# M701X.net
KiCad netlist of a schematic drawn in EAGLE
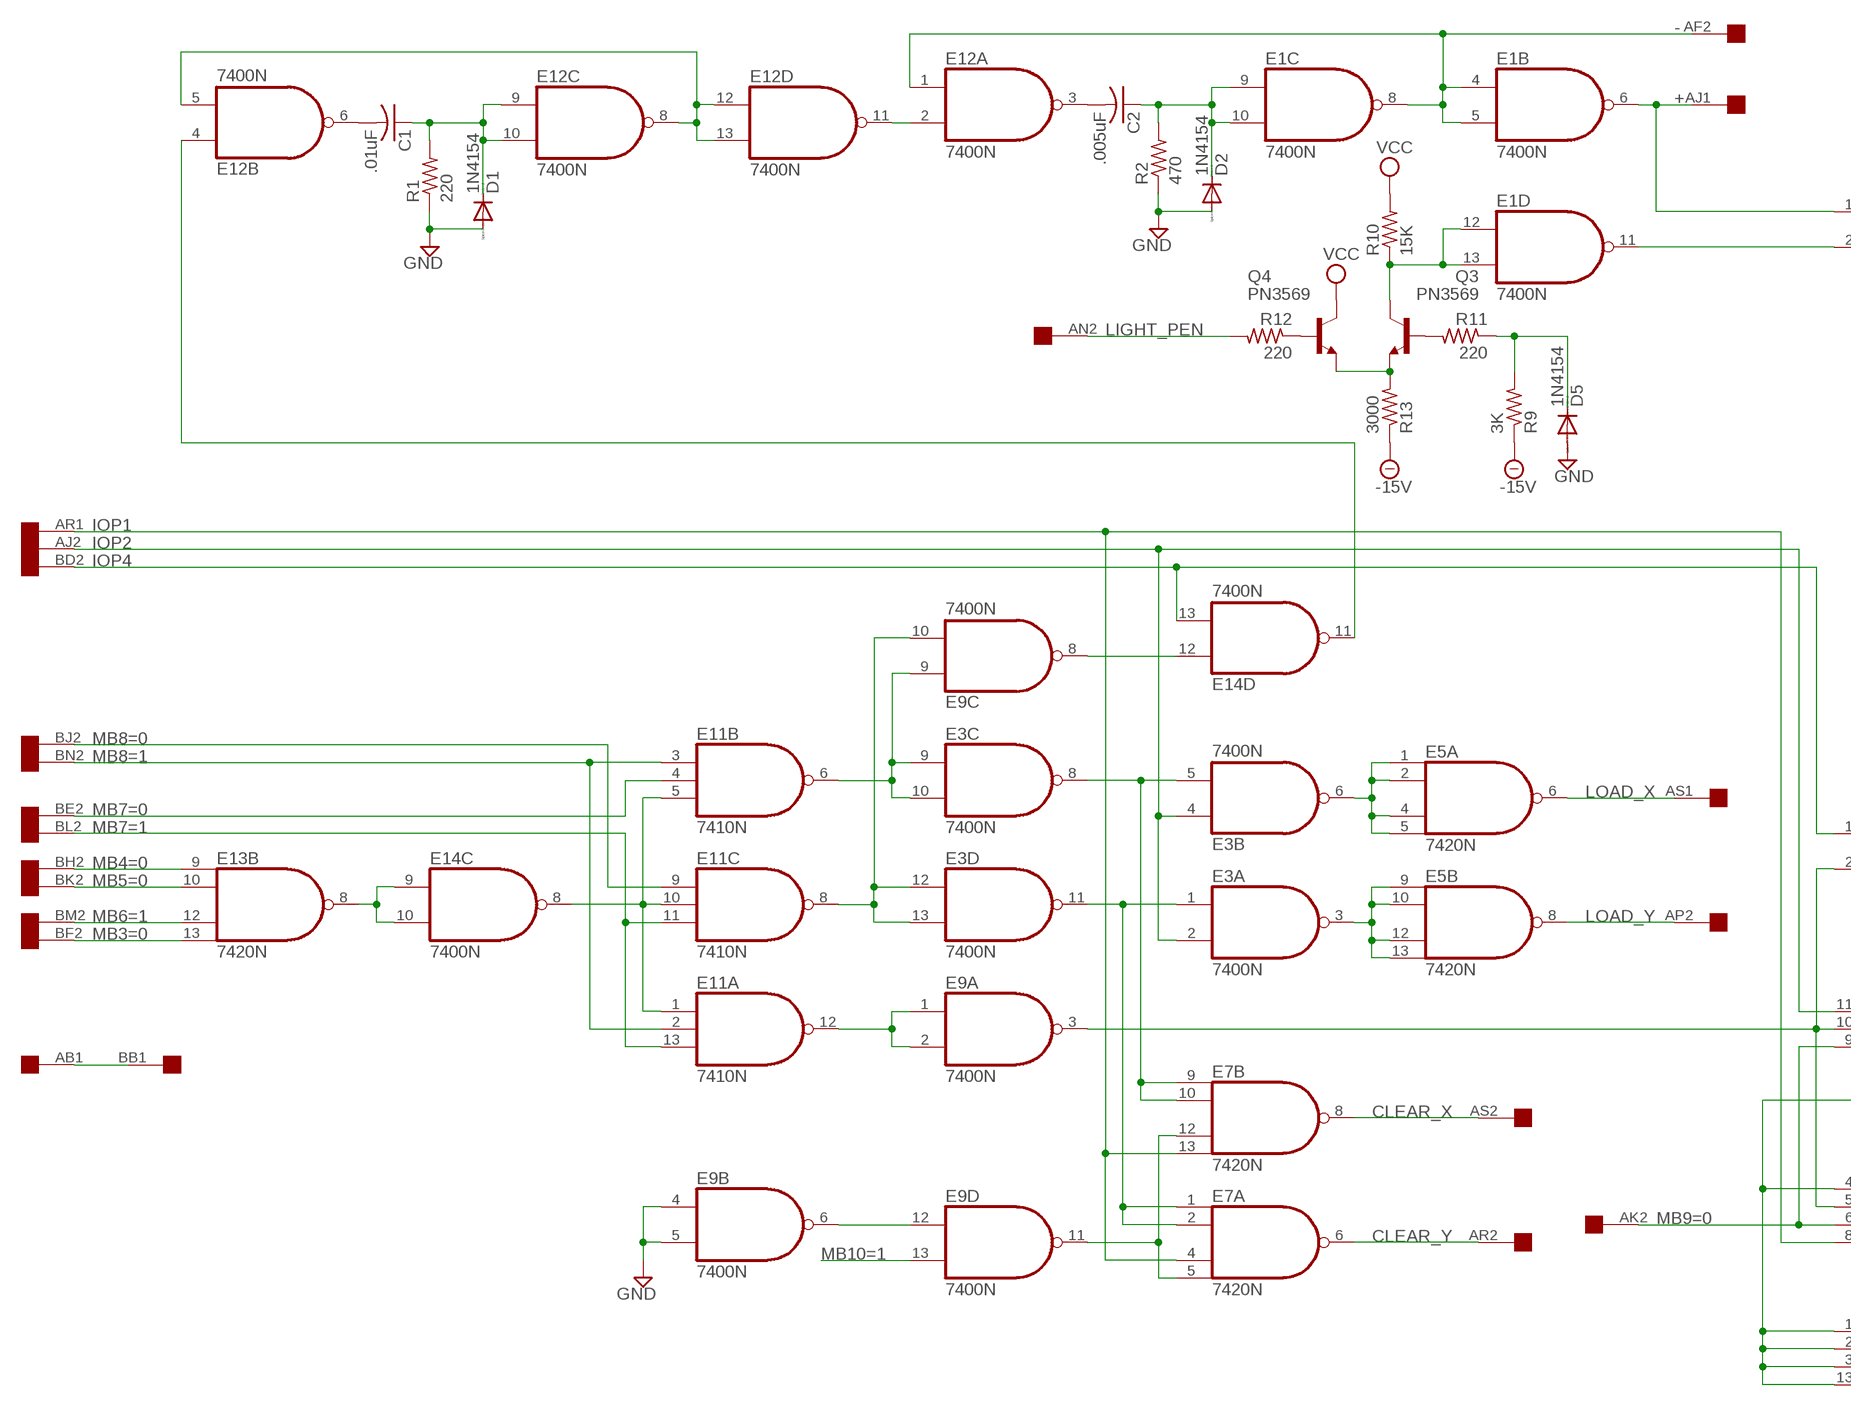
[diagram p0: schematic, sheet 1, part 1 of 2]
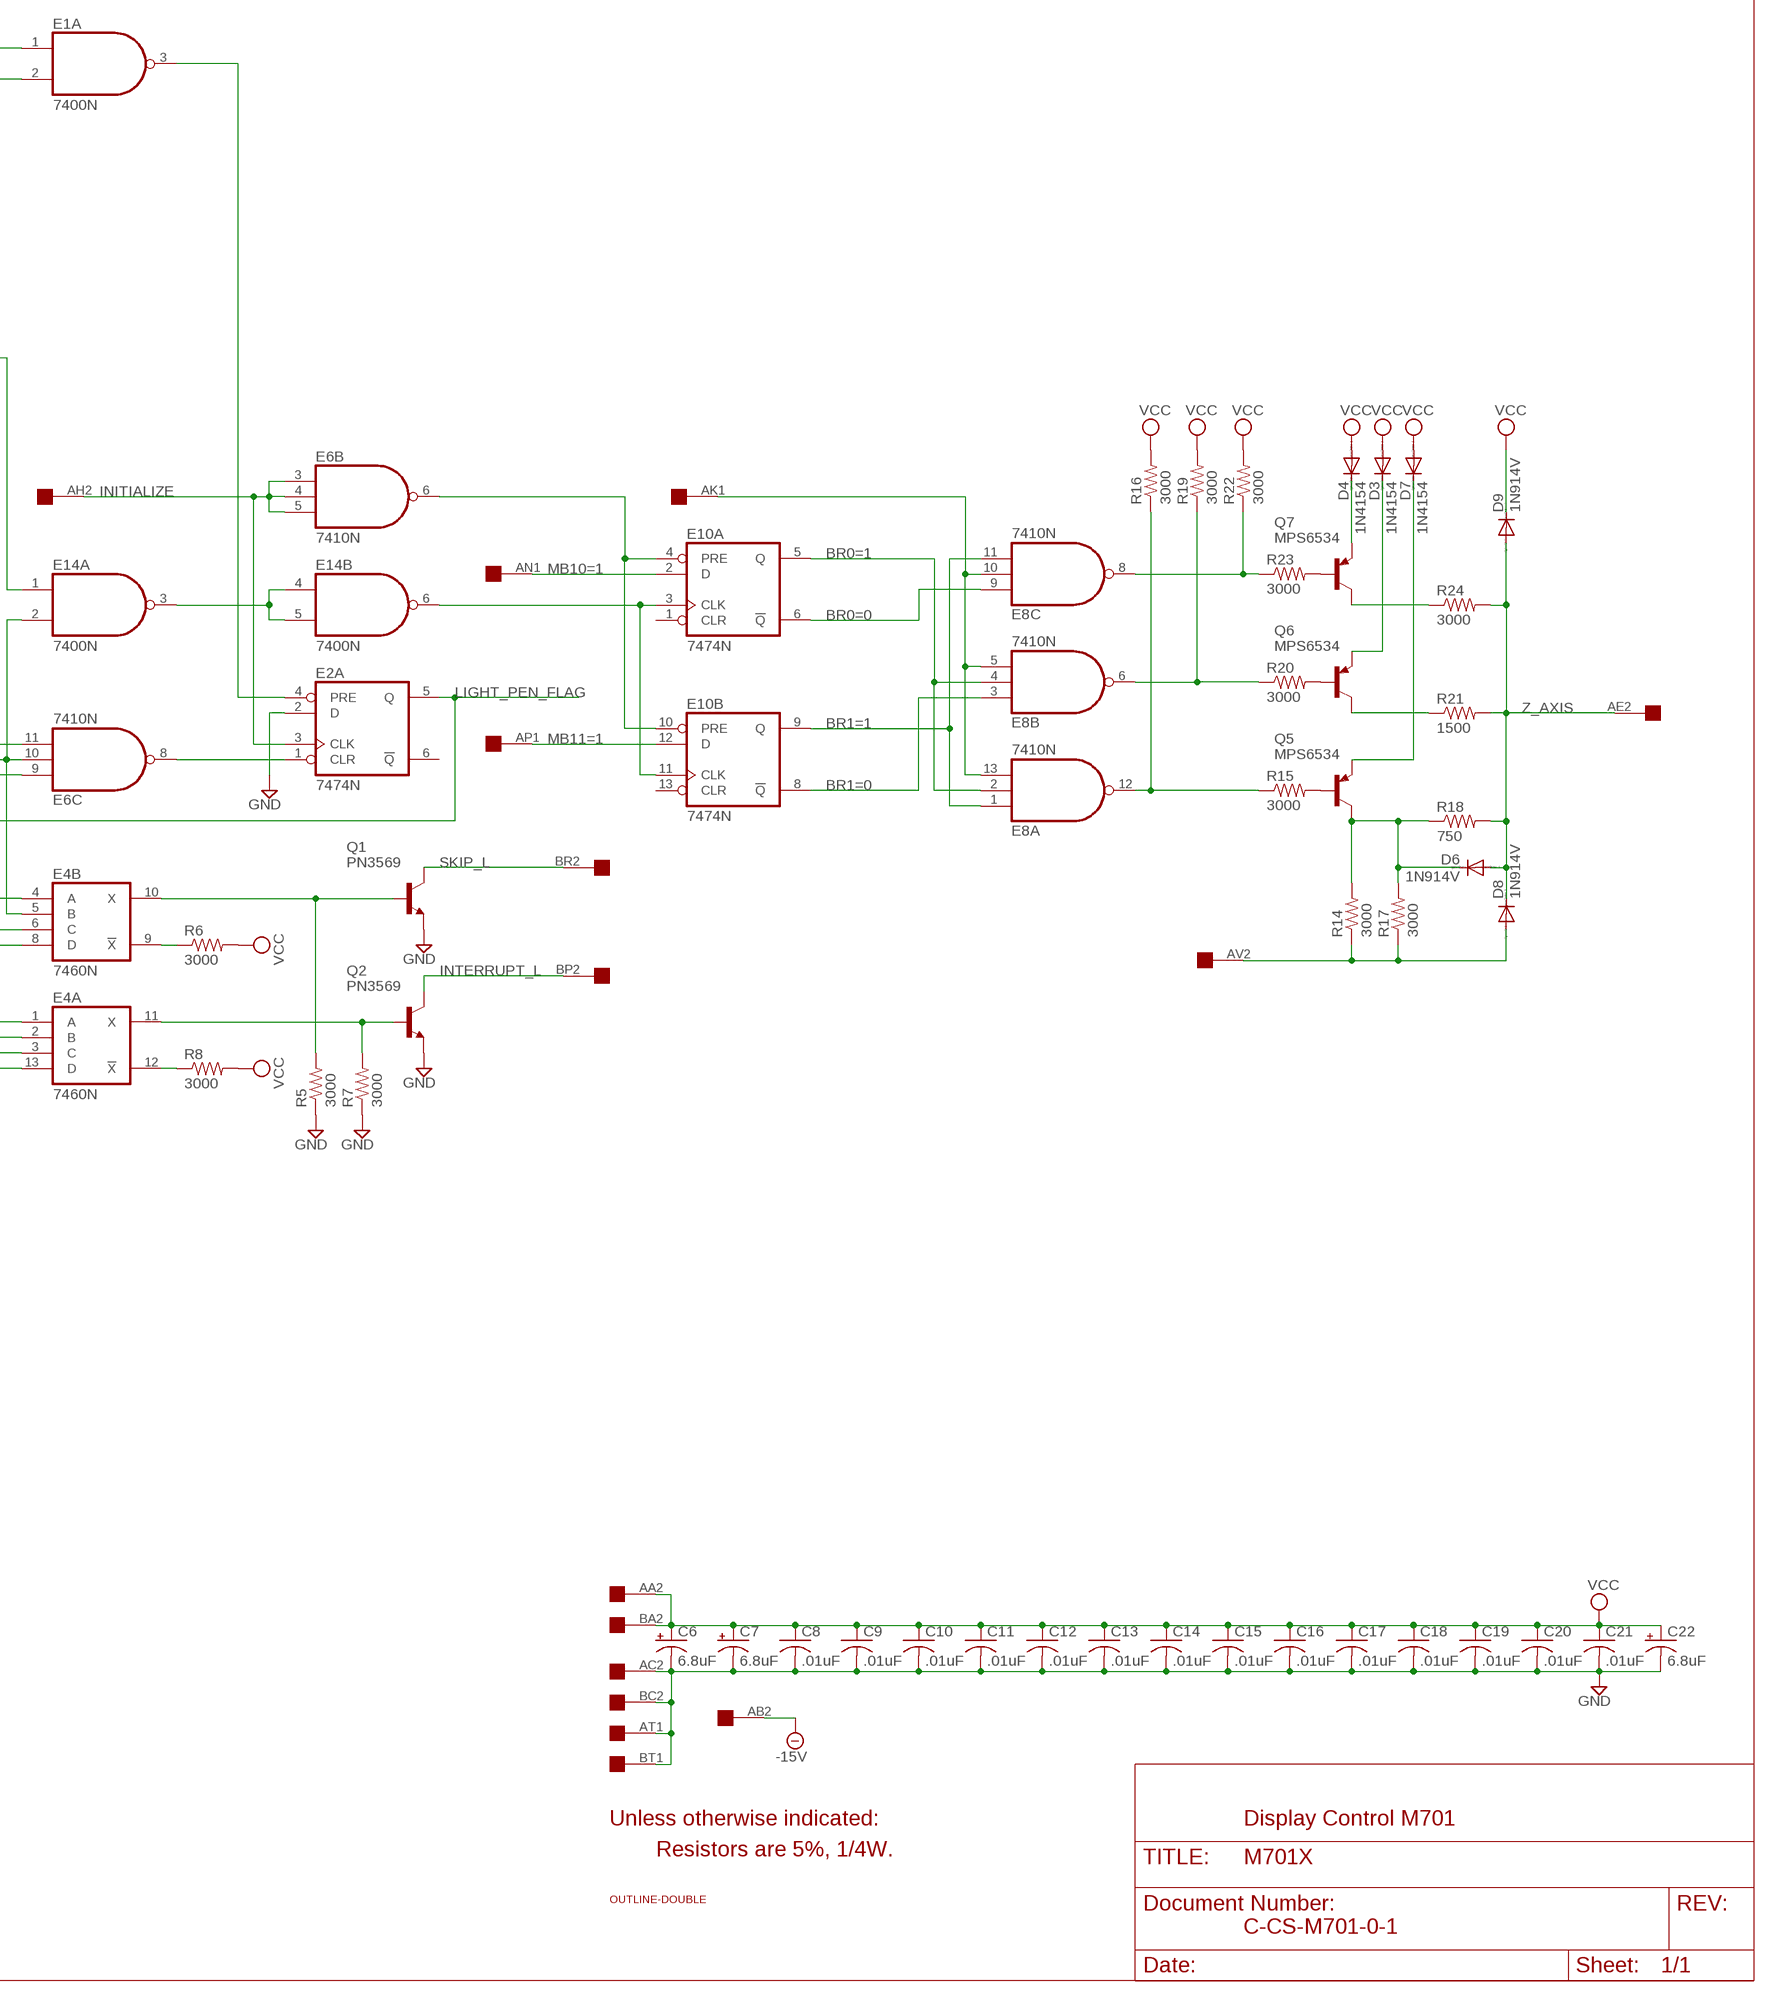
[diagram p1: schematic, sheet 1, part 2 of 2]

(export (version "E")
  (design (tool "Eeschema 10.0.6"))
  (components
    (comp (ref "C1")
      (value ".01uF")
      (footprint "eagle-import:C050-025X075")
      (libsource (lib "eagle-import") (part "C-US050-025X075"))
    )
    (comp (ref "C2")
      (value ".005uF")
      (footprint "eagle-import:C050-025X075")
      (libsource (lib "eagle-import") (part "C-US050-025X075"))
    )
    (comp (ref "C6")
      (value "6.8uF")
      (footprint "eagle-import:E12-8")
      (libsource (lib "eagle-import") (part "CPOL-USE20-8AXIAL"))
    )
    (comp (ref "C7")
      (value "6.8uF")
      (footprint "eagle-import:E12-8")
      (libsource (lib "eagle-import") (part "CPOL-USE20-8AXIAL"))
    )
    (comp (ref "C8")
      (value ".01uF")
      (footprint "eagle-import:C050-025X075")
      (libsource (lib "eagle-import") (part "C-US050-025X075"))
    )
    (comp (ref "C9")
      (value ".01uF")
      (footprint "eagle-import:C050-025X075")
      (libsource (lib "eagle-import") (part "C-US050-025X075"))
    )
    (comp (ref "C10")
      (value ".01uF")
      (footprint "eagle-import:C050-025X075")
      (libsource (lib "eagle-import") (part "C-US050-025X075"))
    )
    (comp (ref "C11")
      (value ".01uF")
      (footprint "eagle-import:C050-025X075")
      (libsource (lib "eagle-import") (part "C-US050-025X075"))
    )
    (comp (ref "C12")
      (value ".01uF")
      (footprint "eagle-import:C050-025X075")
      (libsource (lib "eagle-import") (part "C-US050-025X075"))
    )
    (comp (ref "C13")
      (value ".01uF")
      (footprint "eagle-import:C050-025X075")
      (libsource (lib "eagle-import") (part "C-US050-025X075"))
    )
    (comp (ref "C14")
      (value ".01uF")
      (footprint "eagle-import:C050-025X075")
      (libsource (lib "eagle-import") (part "C-US050-025X075"))
    )
    (comp (ref "C15")
      (value ".01uF")
      (footprint "eagle-import:C050-025X075")
      (libsource (lib "eagle-import") (part "C-US050-025X075"))
    )
    (comp (ref "C16")
      (value ".01uF")
      (footprint "eagle-import:C050-025X075")
      (libsource (lib "eagle-import") (part "C-US050-025X075"))
    )
    (comp (ref "C17")
      (value ".01uF")
      (footprint "eagle-import:C050-025X075")
      (libsource (lib "eagle-import") (part "C-US050-025X075"))
    )
    (comp (ref "C18")
      (value ".01uF")
      (footprint "eagle-import:C050-025X075")
      (libsource (lib "eagle-import") (part "C-US050-025X075"))
    )
    (comp (ref "C19")
      (value ".01uF")
      (footprint "eagle-import:C050-025X075")
      (libsource (lib "eagle-import") (part "C-US050-025X075"))
    )
    (comp (ref "C20")
      (value ".01uF")
      (footprint "eagle-import:C050-025X075")
      (libsource (lib "eagle-import") (part "C-US050-025X075"))
    )
    (comp (ref "C21")
      (value ".01uF")
      (footprint "eagle-import:C050-025X075")
      (libsource (lib "eagle-import") (part "C-US050-025X075"))
    )
    (comp (ref "C22")
      (value "6.8uF")
      (footprint "eagle-import:E12-8")
      (libsource (lib "eagle-import") (part "CPOL-USE20-8AXIAL"))
    )
    (comp (ref "D1")
      (value "1N4154")
      (footprint "eagle-import:DO35-10")
      (libsource (lib "eagle-import") (part "1N4148DO35-10"))
    )
    (comp (ref "D2")
      (value "1N4154")
      (footprint "eagle-import:DO35-10")
      (libsource (lib "eagle-import") (part "1N4148DO35-10"))
    )
    (comp (ref "D3")
      (value "1N4154")
      (footprint "eagle-import:DO35-10")
      (libsource (lib "eagle-import") (part "1N4148DO35-10"))
    )
    (comp (ref "D4")
      (value "1N4154")
      (footprint "eagle-import:DO35-10")
      (libsource (lib "eagle-import") (part "1N4148DO35-10"))
    )
    (comp (ref "D5")
      (value "1N4154")
      (footprint "eagle-import:DO35-10")
      (libsource (lib "eagle-import") (part "1N4148DO35-10"))
    )
    (comp (ref "D6")
      (value "1N914V")
      (footprint "eagle-import:DO35-10")
      (libsource (lib "eagle-import") (part "1N4148DO35-10"))
    )
    (comp (ref "D7")
      (value "1N4154")
      (footprint "eagle-import:DO35-10")
      (libsource (lib "eagle-import") (part "1N4148DO35-10"))
    )
    (comp (ref "D8")
      (value "1N914V")
      (footprint "eagle-import:DO35-10")
      (libsource (lib "eagle-import") (part "1N4148DO35-10"))
    )
    (comp (ref "D9")
      (value "1N914V")
      (footprint "eagle-import:DO35-10")
      (libsource (lib "eagle-import") (part "1N4148DO35-10"))
    )
    (comp (ref "E1")
      (value "7400N")
      (footprint "eagle-import:DIL14")
      (libsource (lib "eagle-import") (part "7400N"))
    )
    (comp (ref "E2")
      (value "7474N")
      (footprint "eagle-import:DIL14")
      (libsource (lib "eagle-import") (part "7474NS"))
    )
    (comp (ref "E3")
      (value "7400N")
      (footprint "eagle-import:DIL14")
      (libsource (lib "eagle-import") (part "7400N"))
    )
    (comp (ref "E4")
      (value "7460N")
      (footprint "eagle-import:DIL14")
      (libsource (lib "eagle-import") (part "7460N"))
    )
    (comp (ref "E5")
      (value "7420N")
      (footprint "eagle-import:DIL14")
      (libsource (lib "eagle-import") (part "7420NS"))
    )
    (comp (ref "E6")
      (value "7410N")
      (footprint "eagle-import:DIL14")
      (libsource (lib "eagle-import") (part "7410N"))
    )
    (comp (ref "E7")
      (value "7420N")
      (footprint "eagle-import:DIL14")
      (libsource (lib "eagle-import") (part "7420NS"))
    )
    (comp (ref "E8")
      (value "7410N")
      (footprint "eagle-import:DIL14")
      (libsource (lib "eagle-import") (part "7410N"))
    )
    (comp (ref "E9")
      (value "7400N")
      (footprint "eagle-import:DIL14")
      (libsource (lib "eagle-import") (part "7400N"))
    )
    (comp (ref "E10")
      (value "7474N")
      (footprint "eagle-import:DIL14")
      (libsource (lib "eagle-import") (part "7474NS"))
    )
    (comp (ref "E11")
      (value "7410N")
      (footprint "eagle-import:DIL14")
      (libsource (lib "eagle-import") (part "7410N"))
    )
    (comp (ref "E12")
      (value "7400N")
      (footprint "eagle-import:DIL14")
      (libsource (lib "eagle-import") (part "7400N"))
    )
    (comp (ref "E13")
      (value "7420N")
      (footprint "eagle-import:DIL14")
      (libsource (lib "eagle-import") (part "7420NS"))
    )
    (comp (ref "E14")
      (value "7400N")
      (footprint "eagle-import:DIL14")
      (libsource (lib "eagle-import") (part "7400N"))
    )
    (comp (ref "Q1")
      (value "PN3569")
      (footprint "eagle-import:TO5")
      (libsource (lib "eagle-import") (part "2N2102"))
    )
    (comp (ref "Q2")
      (value "PN3569")
      (footprint "eagle-import:TO5")
      (libsource (lib "eagle-import") (part "2N2102"))
    )
    (comp (ref "Q3")
      (value "PN3569")
      (footprint "eagle-import:TO5")
      (libsource (lib "eagle-import") (part "2N2102"))
    )
    (comp (ref "Q4")
      (value "PN3569")
      (footprint "eagle-import:TO5")
      (libsource (lib "eagle-import") (part "2N2102"))
    )
    (comp (ref "Q5")
      (value "MPS6534")
      (footprint "eagle-import:TO5")
      (libsource (lib "eagle-import") (part "2N2905"))
    )
    (comp (ref "Q6")
      (value "MPS6534")
      (footprint "eagle-import:TO5")
      (libsource (lib "eagle-import") (part "2N2905"))
    )
    (comp (ref "Q7")
      (value "MPS6534")
      (footprint "eagle-import:TO5")
      (libsource (lib "eagle-import") (part "2N2905"))
    )
    (comp (ref "R1")
      (value "220")
      (footprint "eagle-import:0207_10")
      (libsource (lib "eagle-import") (part "R-US_0207/10"))
    )
    (comp (ref "R2")
      (value "470")
      (footprint "eagle-import:0207_10")
      (libsource (lib "eagle-import") (part "R-US_0207/10"))
    )
    (comp (ref "R5")
      (value "3000")
      (footprint "eagle-import:0207_10")
      (libsource (lib "eagle-import") (part "R-US_0207/10"))
    )
    (comp (ref "R6")
      (value "3000")
      (footprint "eagle-import:0207_10")
      (libsource (lib "eagle-import") (part "R-US_0207/10"))
    )
    (comp (ref "R7")
      (value "3000")
      (footprint "eagle-import:0207_10")
      (libsource (lib "eagle-import") (part "R-US_0207/10"))
    )
    (comp (ref "R8")
      (value "3000")
      (footprint "eagle-import:0207_10")
      (libsource (lib "eagle-import") (part "R-US_0207/10"))
    )
    (comp (ref "R9")
      (value "3K")
      (footprint "eagle-import:0207_10")
      (libsource (lib "eagle-import") (part "R-US_0207/10"))
    )
    (comp (ref "R10")
      (value "15K")
      (footprint "eagle-import:0207_10")
      (libsource (lib "eagle-import") (part "R-US_0207/10"))
    )
    (comp (ref "R11")
      (value "220")
      (footprint "eagle-import:0207_10")
      (libsource (lib "eagle-import") (part "R-US_0207/10"))
    )
    (comp (ref "R12")
      (value "220")
      (footprint "eagle-import:0207_10")
      (libsource (lib "eagle-import") (part "R-US_0207/10"))
    )
    (comp (ref "R13")
      (value "3000")
      (footprint "eagle-import:0207_10")
      (libsource (lib "eagle-import") (part "R-US_0207/10"))
    )
    (comp (ref "R14")
      (value "3000")
      (footprint "eagle-import:0207_10")
      (libsource (lib "eagle-import") (part "R-US_0207/10"))
    )
    (comp (ref "R15")
      (value "3000")
      (footprint "eagle-import:0207_10")
      (libsource (lib "eagle-import") (part "R-US_0207/10"))
    )
    (comp (ref "R16")
      (value "3000")
      (footprint "eagle-import:0207_10")
      (libsource (lib "eagle-import") (part "R-US_0207/10"))
    )
    (comp (ref "R17")
      (value "3000")
      (footprint "eagle-import:0207_10")
      (libsource (lib "eagle-import") (part "R-US_0207/10"))
    )
    (comp (ref "R18")
      (value "750")
      (footprint "eagle-import:0207_10")
      (libsource (lib "eagle-import") (part "R-US_0207/10"))
    )
    (comp (ref "R19")
      (value "3000")
      (footprint "eagle-import:0207_10")
      (libsource (lib "eagle-import") (part "R-US_0207/10"))
    )
    (comp (ref "R20")
      (value "3000")
      (footprint "eagle-import:0207_10")
      (libsource (lib "eagle-import") (part "R-US_0207/10"))
    )
    (comp (ref "R21")
      (value "1500")
      (footprint "eagle-import:0207_10")
      (libsource (lib "eagle-import") (part "R-US_0207/10"))
    )
    (comp (ref "R22")
      (value "3000")
      (footprint "eagle-import:0207_10")
      (libsource (lib "eagle-import") (part "R-US_0207/10"))
    )
    (comp (ref "R23")
      (value "3000")
      (footprint "eagle-import:0207_10")
      (libsource (lib "eagle-import") (part "R-US_0207/10"))
    )
    (comp (ref "R24")
      (value "3000")
      (footprint "eagle-import:0207_10")
      (libsource (lib "eagle-import") (part "R-US_0207/10"))
    )
    (comp (ref "U$1")
      (value "DOUBLE")
      (footprint "eagle-import:EDGE-CON4")
      (libsource (lib "eagle-import") (part "DOUBLE"))
    )
    (comp (ref "U$2")
      (value "OUTLINE-DOUBLE")
      (footprint "eagle-import:DOUBLE")
      (libsource (lib "eagle-import") (part "OUTLINE-DOUBLE"))
    )
  )
  (nets
    (net (code "1") (name "-15V") (class "Default")
      (node (ref "R13") (pin "1") (pinfunction "1_1") (pintype "passive"))
      (node (ref "R9") (pin "1") (pinfunction "1_1") (pintype "passive"))
      (node (ref "U$1") (pin "AB2") (pinfunction "1_AB2") (pintype "bidirectional"))
    )
    (net (code "2") (name "/+") (class "Default")
      (node (ref "E1") (pin "1") (pinfunction "I0_1") (pintype "input"))
      (node (ref "E1") (pin "6") (pinfunction "O_6") (pintype "output"))
      (node (ref "U$1") (pin "AJ1") (pinfunction "1_AJ1") (pintype "bidirectional"))
    )
    (net (code "3") (name "/-") (class "Default")
      (node (ref "E1") (pin "4") (pinfunction "I0_4") (pintype "input"))
      (node (ref "E1") (pin "5") (pinfunction "I1_5") (pintype "input"))
      (node (ref "E1") (pin "8") (pinfunction "O_8") (pintype "output"))
      (node (ref "E12") (pin "1") (pinfunction "I0_1") (pintype "input"))
      (node (ref "U$1") (pin "AF2") (pinfunction "1_AF2") (pintype "bidirectional"))
    )
    (net (code "4") (name "/BR0=0") (class "Default")
      (node (ref "E10") (pin "6") (pinfunction "~{Q}_6") (pintype "output"))
      (node (ref "E8") (pin "9") (pinfunction "I0_9") (pintype "input"))
    )
    (net (code "5") (name "/BR0=1") (class "Default")
      (node (ref "E10") (pin "5") (pinfunction "Q_5") (pintype "output"))
      (node (ref "E8") (pin "2") (pinfunction "I1_2") (pintype "input"))
      (node (ref "E8") (pin "4") (pinfunction "I1_4") (pintype "input"))
    )
    (net (code "6") (name "/BR1=0") (class "Default")
      (node (ref "E10") (pin "8") (pinfunction "~{Q}_8") (pintype "output"))
      (node (ref "E8") (pin "3") (pinfunction "I0_3") (pintype "input"))
    )
    (net (code "7") (name "/BR1=1") (class "Default")
      (node (ref "E10") (pin "9") (pinfunction "Q_9") (pintype "output"))
      (node (ref "E8") (pin "1") (pinfunction "I0_1") (pintype "input"))
      (node (ref "E8") (pin "11") (pinfunction "I2_11") (pintype "input"))
    )
    (net (code "8") (name "/CLEAR_X") (class "Default")
      (node (ref "E7") (pin "8") (pinfunction "O_8") (pintype "output"))
      (node (ref "U$1") (pin "AS2") (pinfunction "1_AS2") (pintype "bidirectional"))
    )
    (net (code "9") (name "/CLEAR_Y") (class "Default")
      (node (ref "E7") (pin "6") (pinfunction "O_6") (pintype "output"))
      (node (ref "U$1") (pin "AR2") (pinfunction "1_AR2") (pintype "bidirectional"))
    )
    (net (code "10") (name "/INITIALIZE") (class "Default")
      (node (ref "E2") (pin "3") (pinfunction "CLK_3") (pintype "input"))
      (node (ref "E6") (pin "3") (pinfunction "I0_3") (pintype "input"))
      (node (ref "E6") (pin "4") (pinfunction "I1_4") (pintype "input"))
      (node (ref "E6") (pin "5") (pinfunction "I2_5") (pintype "input"))
      (node (ref "U$1") (pin "AH2") (pinfunction "1_AH2") (pintype "bidirectional"))
    )
    (net (code "11") (name "/INTERRUPT_L") (class "Default")
      (node (ref "Q2") (pin "3") (pinfunction "C_3") (pintype "passive"))
      (node (ref "U$1") (pin "BP2") (pinfunction "1_BP2") (pintype "bidirectional"))
    )
    (net (code "12") (name "/IOP1") (class "Default")
      (node (ref "E4") (pin "8") (pinfunction "D_8") (pintype "input"))
      (node (ref "E7") (pin "13") (pinfunction "I3_13") (pintype "input"))
      (node (ref "E7") (pin "4") (pinfunction "I2_4") (pintype "input"))
      (node (ref "U$1") (pin "AR1") (pinfunction "1_AR1") (pintype "bidirectional"))
    )
    (net (code "13") (name "/IOP2") (class "Default")
      (node (ref "E3") (pin "2") (pinfunction "I1_2") (pintype "input"))
      (node (ref "E3") (pin "4") (pinfunction "I0_4") (pintype "input"))
      (node (ref "E6") (pin "11") (pinfunction "I2_11") (pintype "input"))
      (node (ref "U$1") (pin "AJ2") (pinfunction "1_AJ2") (pintype "bidirectional"))
    )
    (net (code "14") (name "/IOP4") (class "Default")
      (node (ref "E14") (pin "1") (pinfunction "I0_1") (pintype "input"))
      (node (ref "E14") (pin "13") (pinfunction "I1_13") (pintype "input"))
      (node (ref "U$1") (pin "BD2") (pinfunction "1_BD2") (pintype "bidirectional"))
    )
    (net (code "15") (name "/LIGHT_PEN") (class "Default")
      (node (ref "R12") (pin "2") (pinfunction "2_2") (pintype "passive"))
      (node (ref "U$1") (pin "AN2") (pinfunction "1_AN2") (pintype "bidirectional"))
    )
    (net (code "16") (name "/LIGHT_PEN_FLAG") (class "Default")
      (node (ref "E2") (pin "5") (pinfunction "Q_5") (pintype "output"))
      (node (ref "E4") (pin "1") (pinfunction "A_1") (pintype "input"))
      (node (ref "E4") (pin "13") (pinfunction "D_13") (pintype "input"))
      (node (ref "E4") (pin "2") (pinfunction "B_2") (pintype "input"))
      (node (ref "E4") (pin "3") (pinfunction "C_3") (pintype "input"))
      (node (ref "E4") (pin "4") (pinfunction "A_4") (pintype "input"))
    )
    (net (code "17") (name "/LOAD_X") (class "Default")
      (node (ref "E5") (pin "6") (pinfunction "O_6") (pintype "output"))
      (node (ref "U$1") (pin "AS1") (pinfunction "1_AS1") (pintype "bidirectional"))
    )
    (net (code "18") (name "/LOAD_Y") (class "Default")
      (node (ref "E5") (pin "8") (pinfunction "O_8") (pintype "output"))
      (node (ref "U$1") (pin "AP2") (pinfunction "1_AP2") (pintype "bidirectional"))
    )
    (net (code "19") (name "/MB3=0") (class "Default")
      (node (ref "E13") (pin "13") (pinfunction "I3_13") (pintype "input"))
      (node (ref "U$1") (pin "BF2") (pinfunction "1_BF2") (pintype "bidirectional"))
    )
    (net (code "20") (name "/MB4=0") (class "Default")
      (node (ref "E13") (pin "9") (pinfunction "I0_9") (pintype "input"))
      (node (ref "U$1") (pin "BH2") (pinfunction "1_BH2") (pintype "bidirectional"))
    )
    (net (code "21") (name "/MB5=0") (class "Default")
      (node (ref "E13") (pin "10") (pinfunction "I1_10") (pintype "input"))
      (node (ref "U$1") (pin "BK2") (pinfunction "1_BK2") (pintype "bidirectional"))
    )
    (net (code "22") (name "/MB6=1") (class "Default")
      (node (ref "E13") (pin "12") (pinfunction "I2_12") (pintype "input"))
      (node (ref "U$1") (pin "BM2") (pinfunction "1_BM2") (pintype "bidirectional"))
    )
    (net (code "23") (name "/MB7=0") (class "Default")
      (node (ref "E11") (pin "4") (pinfunction "I1_4") (pintype "input"))
      (node (ref "U$1") (pin "BE2") (pinfunction "1_BE2") (pintype "bidirectional"))
    )
    (net (code "24") (name "/MB7=1") (class "Default")
      (node (ref "E11") (pin "11") (pinfunction "I2_11") (pintype "input"))
      (node (ref "E11") (pin "13") (pinfunction "I2_13") (pintype "input"))
      (node (ref "U$1") (pin "BL2") (pinfunction "1_BL2") (pintype "bidirectional"))
    )
    (net (code "25") (name "/MB8=0") (class "Default")
      (node (ref "E11") (pin "9") (pinfunction "I0_9") (pintype "input"))
      (node (ref "U$1") (pin "BJ2") (pinfunction "1_BJ2") (pintype "bidirectional"))
    )
    (net (code "26") (name "/MB8=1") (class "Default")
      (node (ref "E11") (pin "2") (pinfunction "I1_2") (pintype "input"))
      (node (ref "E11") (pin "3") (pinfunction "I0_3") (pintype "input"))
      (node (ref "U$1") (pin "BN2") (pinfunction "1_BN2") (pintype "bidirectional"))
    )
    (net (code "27") (name "/MB9=0") (class "Default")
      (node (ref "E4") (pin "6") (pinfunction "C_6") (pintype "input"))
      (node (ref "E6") (pin "9") (pinfunction "I0_9") (pintype "input"))
      (node (ref "U$1") (pin "AK2") (pinfunction "1_AK2") (pintype "bidirectional"))
    )
    (net (code "28") (name "/MB10=1") (class "Default")
      (node (ref "E10") (pin "2") (pinfunction "D_2") (pintype "input"))
      (node (ref "E9") (pin "13") (pinfunction "I1_13") (pintype "input"))
      (node (ref "U$1") (pin "AN1") (pinfunction "1_AN1") (pintype "bidirectional"))
    )
    (net (code "29") (name "/MB11=1") (class "Default")
      (node (ref "E10") (pin "12") (pinfunction "D_12") (pintype "input"))
      (node (ref "U$1") (pin "AP1") (pinfunction "1_AP1") (pintype "bidirectional"))
    )
    (net (code "30") (name "/SKIP_L") (class "Default")
      (node (ref "Q1") (pin "3") (pinfunction "C_3") (pintype "passive"))
      (node (ref "U$1") (pin "BR2") (pinfunction "1_BR2") (pintype "bidirectional"))
    )
    (net (code "31") (name "/Z_AXIS") (class "Default")
      (node (ref "D6") (pin "A") (pinfunction "A_A") (pintype "passive"))
      (node (ref "D8") (pin "C") (pinfunction "C_C") (pintype "passive"))
      (node (ref "D9") (pin "A") (pinfunction "A_A") (pintype "passive"))
      (node (ref "R18") (pin "2") (pinfunction "2_2") (pintype "passive"))
      (node (ref "R21") (pin "2") (pinfunction "2_2") (pintype "passive"))
      (node (ref "R24") (pin "2") (pinfunction "2_2") (pintype "passive"))
      (node (ref "U$1") (pin "AE2") (pinfunction "1_AE2") (pintype "bidirectional"))
    )
    (net (code "32") (name "GND") (class "Default")
      (node (ref "C10") (pin "2") (pinfunction "2_2") (pintype "passive"))
      (node (ref "C11") (pin "2") (pinfunction "2_2") (pintype "passive"))
      (node (ref "C12") (pin "2") (pinfunction "2_2") (pintype "passive"))
      (node (ref "C13") (pin "2") (pinfunction "2_2") (pintype "passive"))
      (node (ref "C14") (pin "2") (pinfunction "2_2") (pintype "passive"))
      (node (ref "C15") (pin "2") (pinfunction "2_2") (pintype "passive"))
      (node (ref "C16") (pin "2") (pinfunction "2_2") (pintype "passive"))
      (node (ref "C17") (pin "2") (pinfunction "2_2") (pintype "passive"))
      (node (ref "C18") (pin "2") (pinfunction "2_2") (pintype "passive"))
      (node (ref "C19") (pin "2") (pinfunction "2_2") (pintype "passive"))
      (node (ref "C20") (pin "2") (pinfunction "2_2") (pintype "passive"))
      (node (ref "C21") (pin "2") (pinfunction "2_2") (pintype "passive"))
      (node (ref "C22") (pin "-") (pinfunction "-_-") (pintype "passive"))
      (node (ref "C6") (pin "-") (pinfunction "-_-") (pintype "passive"))
      (node (ref "C7") (pin "-") (pinfunction "-_-") (pintype "passive"))
      (node (ref "C8") (pin "2") (pinfunction "2_2") (pintype "passive"))
      (node (ref "C9") (pin "2") (pinfunction "2_2") (pintype "passive"))
      (node (ref "D1") (pin "A") (pinfunction "A_A") (pintype "passive"))
      (node (ref "D2") (pin "A") (pinfunction "A_A") (pintype "passive"))
      (node (ref "D5") (pin "A") (pinfunction "A_A") (pintype "passive"))
      (node (ref "E2") (pin "2") (pinfunction "D_2") (pintype "input"))
      (node (ref "E9") (pin "4") (pinfunction "I0_4") (pintype "input"))
      (node (ref "E9") (pin "5") (pinfunction "I1_5") (pintype "input"))
      (node (ref "Q1") (pin "1") (pinfunction "E_1") (pintype "passive"))
      (node (ref "Q2") (pin "1") (pinfunction "E_1") (pintype "passive"))
      (node (ref "R1") (pin "1") (pinfunction "1_1") (pintype "passive"))
      (node (ref "R2") (pin "1") (pinfunction "1_1") (pintype "passive"))
      (node (ref "R5") (pin "1") (pinfunction "1_1") (pintype "passive"))
      (node (ref "R7") (pin "1") (pinfunction "1_1") (pintype "passive"))
      (node (ref "U$1") (pin "AC2") (pinfunction "1_AC2") (pintype "bidirectional"))
      (node (ref "U$1") (pin "AT1") (pinfunction "1_AT1") (pintype "bidirectional"))
      (node (ref "U$1") (pin "BC2") (pinfunction "1_BC2") (pintype "bidirectional"))
      (node (ref "U$1") (pin "BT1") (pinfunction "1_BT1") (pintype "bidirectional"))
    )
    (net (code "33") (name "Net-(D5-PadC)") (class "Default")
      (node (ref "D5") (pin "C") (pinfunction "C_C") (pintype "passive"))
      (node (ref "R11") (pin "1") (pinfunction "1_1") (pintype "passive"))
      (node (ref "R9") (pin "2") (pinfunction "2_2") (pintype "passive"))
    )
    (net (code "34") (name "Net-(E1A-I1)") (class "Default")
      (node (ref "E1") (pin "11") (pinfunction "O_11") (pintype "output"))
      (node (ref "E1") (pin "2") (pinfunction "I1_2") (pintype "input"))
    )
    (net (code "35") (name "Net-(E1A-O)") (class "Default")
      (node (ref "E1") (pin "3") (pinfunction "O_3") (pintype "output"))
      (node (ref "E2") (pin "4") (pinfunction "PRE_4") (pintype "input"))
    )
    (net (code "36") (name "Net-(E1C-I0)") (class "Default")
      (node (ref "C2") (pin "1") (pinfunction "1_1") (pintype "passive"))
      (node (ref "D2") (pin "C") (pinfunction "C_C") (pintype "passive"))
      (node (ref "E1") (pin "10") (pinfunction "I1_10") (pintype "input"))
      (node (ref "E1") (pin "9") (pinfunction "I0_9") (pintype "input"))
      (node (ref "R2") (pin "2") (pinfunction "2_2") (pintype "passive"))
    )
    (net (code "37") (name "Net-(E1D-I0)") (class "Default")
      (node (ref "E1") (pin "12") (pinfunction "I0_12") (pintype "input"))
      (node (ref "E1") (pin "13") (pinfunction "I1_13") (pintype "input"))
      (node (ref "Q3") (pin "3") (pinfunction "C_3") (pintype "passive"))
      (node (ref "R10") (pin "1") (pinfunction "1_1") (pintype "passive"))
    )
    (net (code "38") (name "Net-(E2A-CLR)") (class "Default")
      (node (ref "E2") (pin "1") (pinfunction "CLR_1") (pintype "input"))
      (node (ref "E6") (pin "8") (pinfunction "O_8") (pintype "output"))
    )
    (net (code "39") (name "Net-(E3A-I0)") (class "Default")
      (node (ref "E3") (pin "1") (pinfunction "I0_1") (pintype "input"))
      (node (ref "E3") (pin "11") (pinfunction "O_11") (pintype "output"))
      (node (ref "E7") (pin "1") (pinfunction "I0_1") (pintype "input"))
      (node (ref "E7") (pin "2") (pinfunction "I1_2") (pintype "input"))
    )
    (net (code "40") (name "Net-(E3A-O)") (class "Default")
      (node (ref "E3") (pin "3") (pinfunction "O_3") (pintype "output"))
      (node (ref "E5") (pin "10") (pinfunction "I1_10") (pintype "input"))
      (node (ref "E5") (pin "12") (pinfunction "I2_12") (pintype "input"))
      (node (ref "E5") (pin "13") (pinfunction "I3_13") (pintype "input"))
      (node (ref "E5") (pin "9") (pinfunction "I0_9") (pintype "input"))
    )
    (net (code "41") (name "Net-(E3B-I1)") (class "Default")
      (node (ref "E3") (pin "5") (pinfunction "I1_5") (pintype "input"))
      (node (ref "E3") (pin "8") (pinfunction "O_8") (pintype "output"))
      (node (ref "E7") (pin "10") (pinfunction "I1_10") (pintype "input"))
      (node (ref "E7") (pin "9") (pinfunction "I0_9") (pintype "input"))
    )
    (net (code "42") (name "Net-(E3B-O)") (class "Default")
      (node (ref "E3") (pin "6") (pinfunction "O_6") (pintype "output"))
      (node (ref "E5") (pin "1") (pinfunction "I0_1") (pintype "input"))
      (node (ref "E5") (pin "2") (pinfunction "I1_2") (pintype "input"))
      (node (ref "E5") (pin "4") (pinfunction "I2_4") (pintype "input"))
      (node (ref "E5") (pin "5") (pinfunction "I3_5") (pintype "input"))
    )
    (net (code "43") (name "Net-(E4A-X)") (class "Default")
      (node (ref "E4") (pin "11") (pinfunction "X_11") (pintype "output"))
      (node (ref "Q2") (pin "2") (pinfunction "B_2") (pintype "passive"))
      (node (ref "R7") (pin "2") (pinfunction "2_2") (pintype "passive"))
    )
    (net (code "44") (name "Net-(E4A-~{X})") (class "Default")
      (node (ref "E4") (pin "12") (pinfunction "~{X}_12") (pintype "output"))
      (node (ref "R8") (pin "1") (pinfunction "1_1") (pintype "passive"))
    )
    (net (code "45") (name "Net-(E4B-X)") (class "Default")
      (node (ref "E4") (pin "10") (pinfunction "X_10") (pintype "output"))
      (node (ref "Q1") (pin "2") (pinfunction "B_2") (pintype "passive"))
      (node (ref "R5") (pin "2") (pinfunction "2_2") (pintype "passive"))
    )
    (net (code "46") (name "Net-(E4B-~{X})") (class "Default")
      (node (ref "E4") (pin "9") (pinfunction "~{X}_9") (pintype "output"))
      (node (ref "R6") (pin "1") (pinfunction "1_1") (pintype "passive"))
    )
    (net (code "47") (name "Net-(E7A-I3)") (class "Default")
      (node (ref "E7") (pin "12") (pinfunction "I2_12") (pintype "input"))
      (node (ref "E7") (pin "5") (pinfunction "I3_5") (pintype "input"))
      (node (ref "E9") (pin "11") (pinfunction "O_11") (pintype "output"))
    )
    (net (code "48") (name "Net-(E8A-I2)") (class "Default")
      (node (ref "E8") (pin "10") (pinfunction "I1_10") (pintype "input"))
      (node (ref "E8") (pin "13") (pinfunction "I2_13") (pintype "input"))
      (node (ref "E8") (pin "5") (pinfunction "I2_5") (pintype "input"))
      (node (ref "U$1") (pin "AK1") (pinfunction "1_AK1") (pintype "bidirectional"))
    )
    (net (code "49") (name "Net-(E8A-O)") (class "Default")
      (node (ref "E8") (pin "12") (pinfunction "O_12") (pintype "output"))
      (node (ref "R15") (pin "1") (pinfunction "1_1") (pintype "passive"))
      (node (ref "R16") (pin "1") (pinfunction "1_1") (pintype "passive"))
    )
    (net (code "50") (name "Net-(E8B-O)") (class "Default")
      (node (ref "E8") (pin "6") (pinfunction "O_6") (pintype "output"))
      (node (ref "R19") (pin "1") (pinfunction "1_1") (pintype "passive"))
      (node (ref "R20") (pin "1") (pinfunction "1_1") (pintype "passive"))
    )
    (net (code "51") (name "Net-(E8C-O)") (class "Default")
      (node (ref "E8") (pin "8") (pinfunction "O_8") (pintype "output"))
      (node (ref "R22") (pin "1") (pinfunction "1_1") (pintype "passive"))
      (node (ref "R23") (pin "1") (pinfunction "1_1") (pintype "passive"))
    )
    (net (code "52") (name "Net-(E9B-O)") (class "Default")
      (node (ref "E9") (pin "12") (pinfunction "I0_12") (pintype "input"))
      (node (ref "E9") (pin "6") (pinfunction "O_6") (pintype "output"))
    )
    (net (code "53") (name "Net-(E10A-CLK)") (class "Default")
      (node (ref "E10") (pin "11") (pinfunction "CLK_11") (pintype "input"))
      (node (ref "E10") (pin "3") (pinfunction "CLK_3") (pintype "input"))
      (node (ref "E14") (pin "6") (pinfunction "O_6") (pintype "output"))
    )
    (net (code "54") (name "Net-(E10A-PRE)") (class "Default")
      (node (ref "E10") (pin "10") (pinfunction "PRE_10") (pintype "input"))
      (node (ref "E10") (pin "4") (pinfunction "PRE_4") (pintype "input"))
      (node (ref "E6") (pin "6") (pinfunction "O_6") (pintype "output"))
    )
    (net (code "55") (name "Net-(E11A-I0)") (class "Default")
      (node (ref "E11") (pin "1") (pinfunction "I0_1") (pintype "input"))
      (node (ref "E11") (pin "10") (pinfunction "I1_10") (pintype "input"))
      (node (ref "E11") (pin "5") (pinfunction "I2_5") (pintype "input"))
      (node (ref "E14") (pin "8") (pinfunction "O_8") (pintype "output"))
    )
    (net (code "56") (name "Net-(E11A-O)") (class "Default")
      (node (ref "E11") (pin "12") (pinfunction "O_12") (pintype "output"))
      (node (ref "E9") (pin "1") (pinfunction "I0_1") (pintype "input"))
      (node (ref "E9") (pin "2") (pinfunction "I1_2") (pintype "input"))
    )
    (net (code "57") (name "Net-(E11B-O)") (class "Default")
      (node (ref "E11") (pin "6") (pinfunction "O_6") (pintype "output"))
      (node (ref "E3") (pin "10") (pinfunction "I1_10") (pintype "input"))
      (node (ref "E3") (pin "9") (pinfunction "I0_9") (pintype "input"))
      (node (ref "E9") (pin "9") (pinfunction "I0_9") (pintype "input"))
    )
    (net (code "58") (name "Net-(E11C-O)") (class "Default")
      (node (ref "E11") (pin "8") (pinfunction "O_8") (pintype "output"))
      (node (ref "E3") (pin "12") (pinfunction "I0_12") (pintype "input"))
      (node (ref "E3") (pin "13") (pinfunction "I1_13") (pintype "input"))
      (node (ref "E9") (pin "10") (pinfunction "I1_10") (pintype "input"))
    )
    (net (code "59") (name "Net-(E12A-I1)") (class "Default")
      (node (ref "E12") (pin "11") (pinfunction "O_11") (pintype "output"))
      (node (ref "E12") (pin "2") (pinfunction "I1_2") (pintype "input"))
    )
    (net (code "60") (name "Net-(E12A-O)") (class "Default")
      (node (ref "C2") (pin "2") (pinfunction "2_2") (pintype "passive"))
      (node (ref "E12") (pin "3") (pinfunction "O_3") (pintype "output"))
    )
    (net (code "61") (name "Net-(E12B-I0)") (class "Default")
      (node (ref "E12") (pin "4") (pinfunction "I0_4") (pintype "input"))
      (node (ref "E14") (pin "11") (pinfunction "O_11") (pintype "output"))
    )
    (net (code "62") (name "Net-(E12B-I1)") (class "Default")
      (node (ref "E12") (pin "12") (pinfunction "I0_12") (pintype "input"))
      (node (ref "E12") (pin "13") (pinfunction "I1_13") (pintype "input"))
      (node (ref "E12") (pin "5") (pinfunction "I1_5") (pintype "input"))
      (node (ref "E12") (pin "8") (pinfunction "O_8") (pintype "output"))
    )
    (net (code "63") (name "Net-(E12B-O)") (class "Default")
      (node (ref "C1") (pin "2") (pinfunction "2_2") (pintype "passive"))
      (node (ref "E12") (pin "6") (pinfunction "O_6") (pintype "output"))
    )
    (net (code "64") (name "Net-(E12C-I0)") (class "Default")
      (node (ref "C1") (pin "1") (pinfunction "1_1") (pintype "passive"))
      (node (ref "D1") (pin "C") (pinfunction "C_C") (pintype "passive"))
      (node (ref "E12") (pin "10") (pinfunction "I1_10") (pintype "input"))
      (node (ref "E12") (pin "9") (pinfunction "I0_9") (pintype "input"))
      (node (ref "R1") (pin "2") (pinfunction "2_2") (pintype "passive"))
    )
    (net (code "65") (name "Net-(E13B-O)") (class "Default")
      (node (ref "E13") (pin "8") (pinfunction "O_8") (pintype "output"))
      (node (ref "E14") (pin "10") (pinfunction "I1_10") (pintype "input"))
      (node (ref "E14") (pin "9") (pinfunction "I0_9") (pintype "input"))
    )
    (net (code "66") (name "Net-(E14A-I1)") (class "Default")
      (node (ref "E14") (pin "2") (pinfunction "I1_2") (pintype "input"))
      (node (ref "E4") (pin "5") (pinfunction "B_5") (pintype "input"))
      (node (ref "E6") (pin "10") (pinfunction "I1_10") (pintype "input"))
      (node (ref "E9") (pin "3") (pinfunction "O_3") (pintype "output"))
    )
    (net (code "67") (name "Net-(E14A-O)") (class "Default")
      (node (ref "E14") (pin "3") (pinfunction "O_3") (pintype "output"))
      (node (ref "E14") (pin "4") (pinfunction "I0_4") (pintype "input"))
      (node (ref "E14") (pin "5") (pinfunction "I1_5") (pintype "input"))
    )
    (net (code "68") (name "Net-(E14D-I0)") (class "Default")
      (node (ref "E14") (pin "12") (pinfunction "I0_12") (pintype "input"))
      (node (ref "E9") (pin "8") (pinfunction "O_8") (pintype "output"))
    )
    (net (code "69") (name "Net-(Q3-B)") (class "Default")
      (node (ref "Q3") (pin "2") (pinfunction "B_2") (pintype "passive"))
      (node (ref "R11") (pin "2") (pinfunction "2_2") (pintype "passive"))
    )
    (net (code "70") (name "Net-(Q3-E)") (class "Default")
      (node (ref "Q3") (pin "1") (pinfunction "E_1") (pintype "passive"))
      (node (ref "Q4") (pin "1") (pinfunction "E_1") (pintype "passive"))
      (node (ref "R13") (pin "2") (pinfunction "2_2") (pintype "passive"))
    )
    (net (code "71") (name "Net-(Q4-B)") (class "Default")
      (node (ref "Q4") (pin "2") (pinfunction "B_2") (pintype "passive"))
      (node (ref "R12") (pin "1") (pinfunction "1_1") (pintype "passive"))
    )
    (net (code "72") (name "Net-(Q5-B)") (class "Default")
      (node (ref "Q5") (pin "2") (pinfunction "B_2") (pintype "passive"))
      (node (ref "R15") (pin "2") (pinfunction "2_2") (pintype "passive"))
    )
    (net (code "73") (name "Net-(Q5-C)") (class "Default")
      (node (ref "D6") (pin "C") (pinfunction "C_C") (pintype "passive"))
      (node (ref "Q5") (pin "3") (pinfunction "C_3") (pintype "passive"))
      (node (ref "R14") (pin "2") (pinfunction "2_2") (pintype "passive"))
      (node (ref "R17") (pin "2") (pinfunction "2_2") (pintype "passive"))
      (node (ref "R18") (pin "1") (pinfunction "1_1") (pintype "passive"))
    )
    (net (code "74") (name "Net-(Q5-E)") (class "Default")
      (node (ref "D7") (pin "C") (pinfunction "C_C") (pintype "passive"))
      (node (ref "Q5") (pin "1") (pinfunction "E_1") (pintype "passive"))
    )
    (net (code "75") (name "Net-(Q6-B)") (class "Default")
      (node (ref "Q6") (pin "2") (pinfunction "B_2") (pintype "passive"))
      (node (ref "R20") (pin "2") (pinfunction "2_2") (pintype "passive"))
    )
    (net (code "76") (name "Net-(Q6-C)") (class "Default")
      (node (ref "Q6") (pin "3") (pinfunction "C_3") (pintype "passive"))
      (node (ref "R21") (pin "1") (pinfunction "1_1") (pintype "passive"))
    )
    (net (code "77") (name "Net-(Q6-E)") (class "Default")
      (node (ref "D3") (pin "C") (pinfunction "C_C") (pintype "passive"))
      (node (ref "Q6") (pin "1") (pinfunction "E_1") (pintype "passive"))
    )
    (net (code "78") (name "Net-(Q7-B)") (class "Default")
      (node (ref "Q7") (pin "2") (pinfunction "B_2") (pintype "passive"))
      (node (ref "R23") (pin "2") (pinfunction "2_2") (pintype "passive"))
    )
    (net (code "79") (name "Net-(Q7-C)") (class "Default")
      (node (ref "Q7") (pin "3") (pinfunction "C_3") (pintype "passive"))
      (node (ref "R24") (pin "1") (pinfunction "1_1") (pintype "passive"))
    )
    (net (code "80") (name "Net-(Q7-E)") (class "Default")
      (node (ref "D4") (pin "C") (pinfunction "C_C") (pintype "passive"))
      (node (ref "Q7") (pin "1") (pinfunction "E_1") (pintype "passive"))
    )
    (net (code "81") (name "Net-(U$1AJ-1)") (class "Default")
      (node (ref "D8") (pin "A") (pinfunction "A_A") (pintype "passive"))
      (node (ref "R14") (pin "1") (pinfunction "1_1") (pintype "passive"))
      (node (ref "R17") (pin "1") (pinfunction "1_1") (pintype "passive"))
      (node (ref "U$1") (pin "AV2") (pinfunction "1_AV2") (pintype "bidirectional"))
    )
    (net (code "82") (name "Net-(U$1AM-1)") (class "Default")
      (node (ref "U$1") (pin "AB1") (pinfunction "1_AB1") (pintype "bidirectional"))
      (node (ref "U$1") (pin "BB1") (pinfunction "1_BB1") (pintype "bidirectional"))
    )
    (net (code "83") (name "VCC") (class "Default")
      (node (ref "C10") (pin "1") (pinfunction "1_1") (pintype "passive"))
      (node (ref "C11") (pin "1") (pinfunction "1_1") (pintype "passive"))
      (node (ref "C12") (pin "1") (pinfunction "1_1") (pintype "passive"))
      (node (ref "C13") (pin "1") (pinfunction "1_1") (pintype "passive"))
      (node (ref "C14") (pin "1") (pinfunction "1_1") (pintype "passive"))
      (node (ref "C15") (pin "1") (pinfunction "1_1") (pintype "passive"))
      (node (ref "C16") (pin "1") (pinfunction "1_1") (pintype "passive"))
      (node (ref "C17") (pin "1") (pinfunction "1_1") (pintype "passive"))
      (node (ref "C18") (pin "1") (pinfunction "1_1") (pintype "passive"))
      (node (ref "C19") (pin "1") (pinfunction "1_1") (pintype "passive"))
      (node (ref "C20") (pin "1") (pinfunction "1_1") (pintype "passive"))
      (node (ref "C21") (pin "1") (pinfunction "1_1") (pintype "passive"))
      (node (ref "C22") (pin "+") (pinfunction "+_+") (pintype "passive"))
      (node (ref "C6") (pin "+") (pinfunction "+_+") (pintype "passive"))
      (node (ref "C7") (pin "+") (pinfunction "+_+") (pintype "passive"))
      (node (ref "C8") (pin "1") (pinfunction "1_1") (pintype "passive"))
      (node (ref "C9") (pin "1") (pinfunction "1_1") (pintype "passive"))
      (node (ref "D3") (pin "A") (pinfunction "A_A") (pintype "passive"))
      (node (ref "D4") (pin "A") (pinfunction "A_A") (pintype "passive"))
      (node (ref "D7") (pin "A") (pinfunction "A_A") (pintype "passive"))
      (node (ref "D9") (pin "C") (pinfunction "C_C") (pintype "passive"))
      (node (ref "Q4") (pin "3") (pinfunction "C_3") (pintype "passive"))
      (node (ref "R10") (pin "2") (pinfunction "2_2") (pintype "passive"))
      (node (ref "R16") (pin "2") (pinfunction "2_2") (pintype "passive"))
      (node (ref "R19") (pin "2") (pinfunction "2_2") (pintype "passive"))
      (node (ref "R22") (pin "2") (pinfunction "2_2") (pintype "passive"))
      (node (ref "R6") (pin "2") (pinfunction "2_2") (pintype "passive"))
      (node (ref "R8") (pin "2") (pinfunction "2_2") (pintype "passive"))
      (node (ref "U$1") (pin "AA2") (pinfunction "1_AA2") (pintype "bidirectional"))
      (node (ref "U$1") (pin "BA2") (pinfunction "1_BA2") (pintype "bidirectional"))
    )
    (net (code "84") (name "unconnected-(E2A-~{Q}-Pad6)") (class "Default")
      (node (ref "E2") (pin "6") (pinfunction "~{Q}_6") (pintype "output"))
    )
    (net (code "85") (name "unconnected-(E10A-CLR-Pad1)") (class "Default")
      (node (ref "E10") (pin "1") (pinfunction "CLR_1") (pintype "input"))
    )
    (net (code "86") (name "unconnected-(E10B-CLR-Pad13)") (class "Default")
      (node (ref "E10") (pin "13") (pinfunction "CLR_13") (pintype "input"))
    )
  )
)
